# Usb_otg_fs.net
KiCad netlist of a schematic drawn in Altium Designer
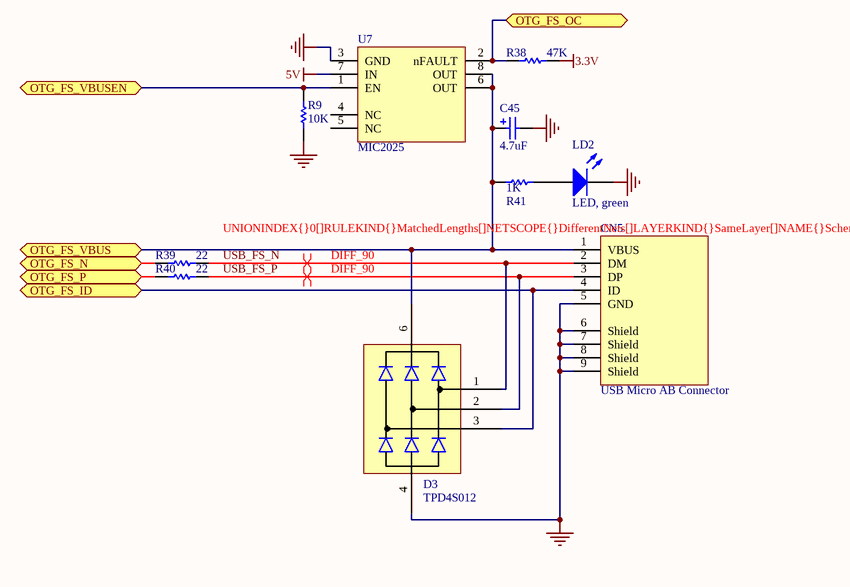
[diagram p0: Usb_otg_fs.SchDoc]

(export (version "E")
  (design (tool "Eeschema 10.0.6"))
  (components
    (comp (ref "C45")
      (value "4.7uF")
      (footprint "TC3216-1206")
      (description "Polarized Capacitor")
      (fields (field (name "Comment") "Cap Pol"))
      (libsource (lib "Core429IBaseBoard") (part "Cap Pol"))
    )
    (comp (ref "CN5")
      (value "USB Micro AB Connector")
      (footprint "ZX62RD-AB-5P8")
      (description "Micro-USB connectors meeting USB 2.0 Standard")
      (libsource (lib "Core429IBaseBoardVerE") (part "USB Micro AB Connector"))
    )
    (comp (ref "D3")
      (value "TPD4S012")
      (footprint "SON50P100X60-6M")
      (description "4-Channel ESD Solution for USB-HS/USB OTG/USB Charger Interface")
      (libsource (lib "Core429IBaseBoardVerF") (part "TPD4S012"))
    )
    (comp (ref "LD2")
      (value "LED, green")
      (footprint "CLED2012-0805")
      (description "Light emitting diode")
      (libsource (lib "Core429IBaseBoard") (part "LED"))
    )
    (comp (ref "R9")
      (value "10K")
      (footprint "RESC2012N")
      (description "Resistor")
      (fields (field (name "Comment") "Res"))
      (libsource (lib "Core429IBaseBoardVerF") (part "Res"))
    )
    (comp (ref "R38")
      (value "47K")
      (footprint "RESC2012N")
      (description "Resistor")
      (fields (field (name "Comment") "1206"))
      (libsource (lib "Core429IBaseBoard") (part "Res"))
    )
    (comp (ref "R39")
      (value "22")
      (footprint "RESC2012N")
      (description "Resistor")
      (fields (field (name "Comment") "1206"))
      (libsource (lib "Core429IBaseBoard") (part "Res"))
    )
    (comp (ref "R40")
      (value "22")
      (footprint "RESC2012N")
      (description "Resistor")
      (fields (field (name "Comment") "1206"))
      (libsource (lib "Core429IBaseBoard") (part "Res"))
    )
    (comp (ref "R41")
      (value "1K")
      (footprint "RESC2012N")
      (description "Resistor")
      (fields (field (name "Comment") "1206"))
      (libsource (lib "Core429IBaseBoard") (part "Res"))
    )
    (comp (ref "U7")
      (value "MIC2025")
      (footprint "SOIC127P600X173-8M")
      (description "Single-Channel Power Distribution Switch MM8")
      (libsource (lib "Core429IBaseBoardVerE") (part "MIC2025"))
    )
  )
  (nets
    (net (code "1") (name "/OTG_FS_ID") (class "Default")
      (node (ref "CN5") (pin "4") (pinfunction "ID_4") (pintype "passive"))
      (node (ref "D3") (pin "3") (pinfunction "3_3") (pintype "passive"))
    )
    (net (code "2") (name "/OTG_FS_N") (class "Default")
      (node (ref "R39") (pin "2") (pinfunction "2_2") (pintype "passive"))
    )
    (net (code "3") (name "/OTG_FS_OC") (class "Default")
      (node (ref "R38") (pin "2") (pinfunction "2_2") (pintype "passive"))
      (node (ref "U7") (pin "2") (pinfunction "nFAULT_2") (pintype "passive"))
    )
    (net (code "4") (name "/OTG_FS_P") (class "Default")
      (node (ref "R40") (pin "2") (pinfunction "2_2") (pintype "passive"))
    )
    (net (code "5") (name "/OTG_FS_VBUS") (class "Default")
      (node (ref "C45") (pin "1") (pinfunction "1_1") (pintype "passive"))
      (node (ref "CN5") (pin "1") (pinfunction "VBUS_1") (pintype "passive"))
      (node (ref "D3") (pin "6") (pinfunction "6_6") (pintype "passive"))
      (node (ref "R41") (pin "2") (pinfunction "2_2") (pintype "passive"))
      (node (ref "U7") (pin "6") (pinfunction "OUT_6") (pintype "passive"))
      (node (ref "U7") (pin "8") (pinfunction "OUT_8") (pintype "passive"))
    )
    (net (code "6") (name "/OTG_FS_VBUSEN") (class "Default")
      (node (ref "R9") (pin "1") (pinfunction "1_1") (pintype "passive"))
      (node (ref "U7") (pin "1") (pinfunction "EN_1") (pintype "passive"))
    )
    (net (code "7") (name "/USB_FS_N") (class "Default")
      (node (ref "CN5") (pin "2") (pinfunction "DM_2") (pintype "passive"))
      (node (ref "D3") (pin "1") (pinfunction "1_1") (pintype "passive"))
      (node (ref "R39") (pin "1") (pinfunction "1_1") (pintype "passive"))
    )
    (net (code "8") (name "/USB_FS_P") (class "Default")
      (node (ref "CN5") (pin "3") (pinfunction "DP_3") (pintype "passive"))
      (node (ref "D3") (pin "2") (pinfunction "2_2") (pintype "passive"))
      (node (ref "R40") (pin "1") (pinfunction "1_1") (pintype "passive"))
    )
    (net (code "9") (name "3.3V") (class "Default")
      (node (ref "R38") (pin "1") (pinfunction "1_1") (pintype "passive"))
    )
    (net (code "10") (name "5V") (class "Default")
      (node (ref "U7") (pin "7") (pinfunction "IN_7") (pintype "passive"))
    )
    (net (code "11") (name "DGND") (class "Default")
      (node (ref "C45") (pin "2") (pinfunction "2_2") (pintype "passive"))
      (node (ref "CN5") (pin "5") (pinfunction "GND_5") (pintype "passive"))
      (node (ref "CN5") (pin "6") (pinfunction "Shield_6") (pintype "passive"))
      (node (ref "CN5") (pin "7") (pinfunction "Shield_7") (pintype "passive"))
      (node (ref "CN5") (pin "8") (pinfunction "Shield_8") (pintype "passive"))
      (node (ref "CN5") (pin "9") (pinfunction "Shield_9") (pintype "passive"))
      (node (ref "D3") (pin "4") (pinfunction "4_4") (pintype "passive"))
      (node (ref "LD2") (pin "2") (pinfunction "K_2") (pintype "passive"))
      (node (ref "R9") (pin "2") (pinfunction "2_2") (pintype "passive"))
      (node (ref "U7") (pin "3") (pinfunction "GND_3") (pintype "passive"))
    )
    (net (code "12") (name "Net-(LD2-A)") (class "Default")
      (node (ref "LD2") (pin "1") (pinfunction "A_1") (pintype "passive"))
      (node (ref "R41") (pin "1") (pinfunction "1_1") (pintype "passive"))
    )
    (net (code "13") (name "unconnected-(U7-NC-Pad4)") (class "Default")
      (node (ref "U7") (pin "4") (pinfunction "NC_4") (pintype "passive"))
    )
    (net (code "14") (name "unconnected-(U7-NC-Pad5)") (class "Default")
      (node (ref "U7") (pin "5") (pinfunction "NC_5") (pintype "passive"))
    )
  )
)
